# W600X.net
KiCad netlist of a schematic drawn in EAGLE
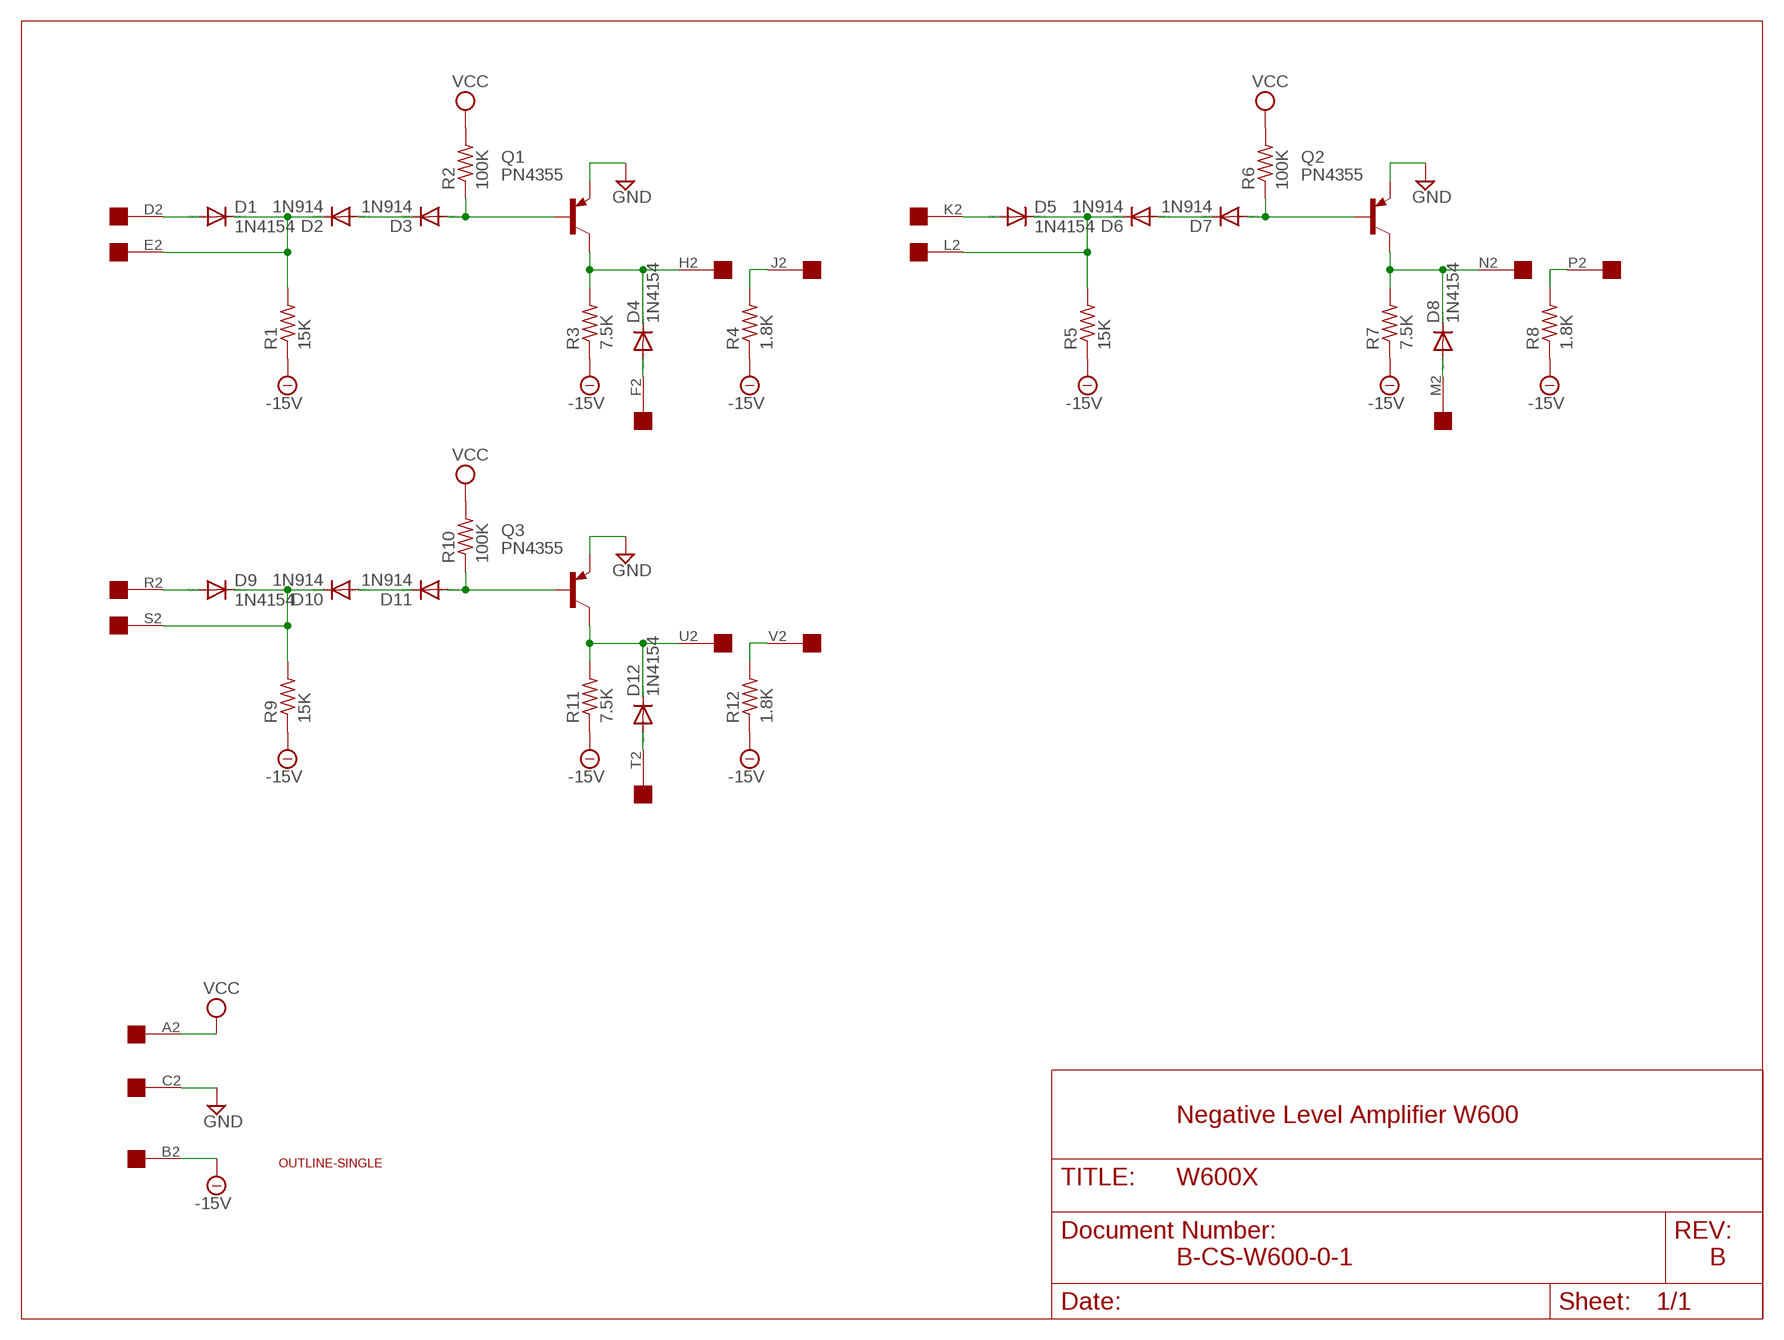
[diagram p0: schematic, sheet 1]

(export (version "E")
  (design (tool "Eeschema 10.0.6"))
  (components
    (comp (ref "D1")
      (value "1N4154")
      (footprint "eagle-import:DO35-10")
      (libsource (lib "eagle-import") (part "DIODE-DO35-10"))
    )
    (comp (ref "D2")
      (value "1N914")
      (footprint "eagle-import:DO35-10")
      (libsource (lib "eagle-import") (part "DIODE-DO35-10"))
    )
    (comp (ref "D3")
      (value "1N914")
      (footprint "eagle-import:DO35-10")
      (libsource (lib "eagle-import") (part "DIODE-DO35-10"))
    )
    (comp (ref "D4")
      (value "1N4154")
      (footprint "eagle-import:DO35-10")
      (libsource (lib "eagle-import") (part "DIODE-DO35-10"))
    )
    (comp (ref "D5")
      (value "1N4154")
      (footprint "eagle-import:DO35-10")
      (libsource (lib "eagle-import") (part "DIODE-DO35-10"))
    )
    (comp (ref "D6")
      (value "1N914")
      (footprint "eagle-import:DO35-10")
      (libsource (lib "eagle-import") (part "DIODE-DO35-10"))
    )
    (comp (ref "D7")
      (value "1N914")
      (footprint "eagle-import:DO35-10")
      (libsource (lib "eagle-import") (part "DIODE-DO35-10"))
    )
    (comp (ref "D8")
      (value "1N4154")
      (footprint "eagle-import:DO35-10")
      (libsource (lib "eagle-import") (part "DIODE-DO35-10"))
    )
    (comp (ref "D9")
      (value "1N4154")
      (footprint "eagle-import:DO35-10")
      (libsource (lib "eagle-import") (part "DIODE-DO35-10"))
    )
    (comp (ref "D10")
      (value "1N914")
      (footprint "eagle-import:DO35-10")
      (libsource (lib "eagle-import") (part "DIODE-DO35-10"))
    )
    (comp (ref "D11")
      (value "1N914")
      (footprint "eagle-import:DO35-10")
      (libsource (lib "eagle-import") (part "DIODE-DO35-10"))
    )
    (comp (ref "D12")
      (value "1N4154")
      (footprint "eagle-import:DO35-10")
      (libsource (lib "eagle-import") (part "DIODE-DO35-10"))
    )
    (comp (ref "Q1")
      (value "PN4355")
      (footprint "eagle-import:TO5")
      (libsource (lib "eagle-import") (part "-PNP-TO5"))
    )
    (comp (ref "Q2")
      (value "PN4355")
      (footprint "eagle-import:TO5")
      (libsource (lib "eagle-import") (part "-PNP-TO5"))
    )
    (comp (ref "Q3")
      (value "PN4355")
      (footprint "eagle-import:TO5")
      (libsource (lib "eagle-import") (part "-PNP-TO5"))
    )
    (comp (ref "R1")
      (value "15K")
      (footprint "eagle-import:0207_10")
      (libsource (lib "eagle-import") (part "R-US_0207/10"))
    )
    (comp (ref "R2")
      (value "100K")
      (footprint "eagle-import:0207_10")
      (libsource (lib "eagle-import") (part "R-US_0207/10"))
    )
    (comp (ref "R3")
      (value "7.5K")
      (footprint "eagle-import:0207_10")
      (libsource (lib "eagle-import") (part "R-US_0207/10"))
    )
    (comp (ref "R4")
      (value "1.8K")
      (footprint "eagle-import:0207_10")
      (libsource (lib "eagle-import") (part "R-US_0207/10"))
    )
    (comp (ref "R5")
      (value "15K")
      (footprint "eagle-import:0207_10")
      (libsource (lib "eagle-import") (part "R-US_0207/10"))
    )
    (comp (ref "R6")
      (value "100K")
      (footprint "eagle-import:0207_10")
      (libsource (lib "eagle-import") (part "R-US_0207/10"))
    )
    (comp (ref "R7")
      (value "7.5K")
      (footprint "eagle-import:0207_10")
      (libsource (lib "eagle-import") (part "R-US_0207/10"))
    )
    (comp (ref "R8")
      (value "1.8K")
      (footprint "eagle-import:0207_10")
      (libsource (lib "eagle-import") (part "R-US_0207/10"))
    )
    (comp (ref "R9")
      (value "15K")
      (footprint "eagle-import:0207_10")
      (libsource (lib "eagle-import") (part "R-US_0207/10"))
    )
    (comp (ref "R10")
      (value "100K")
      (footprint "eagle-import:0207_10")
      (libsource (lib "eagle-import") (part "R-US_0207/10"))
    )
    (comp (ref "R11")
      (value "7.5K")
      (footprint "eagle-import:0207_10")
      (libsource (lib "eagle-import") (part "R-US_0207/10"))
    )
    (comp (ref "R12")
      (value "1.8K")
      (footprint "eagle-import:0207_10")
      (libsource (lib "eagle-import") (part "R-US_0207/10"))
    )
    (comp (ref "U$1")
      (value "OUTLINE-SINGLE")
      (footprint "eagle-import:SINGLE")
      (libsource (lib "eagle-import") (part "OUTLINE-SINGLE"))
    )
    (comp (ref "U$2")
      (value "EDGE-1")
      (footprint "eagle-import:EDGE-CON1")
      (libsource (lib "eagle-import") (part "EDGE-1"))
    )
  )
  (nets
    (net (code "1") (name "-15V") (class "Default")
      (node (ref "R1") (pin "1") (pinfunction "1_1") (pintype "passive"))
      (node (ref "R11") (pin "1") (pinfunction "1_1") (pintype "passive"))
      (node (ref "R12") (pin "1") (pinfunction "1_1") (pintype "passive"))
      (node (ref "R3") (pin "1") (pinfunction "1_1") (pintype "passive"))
      (node (ref "R4") (pin "1") (pinfunction "1_1") (pintype "passive"))
      (node (ref "R5") (pin "1") (pinfunction "1_1") (pintype "passive"))
      (node (ref "R7") (pin "1") (pinfunction "1_1") (pintype "passive"))
      (node (ref "R8") (pin "1") (pinfunction "1_1") (pintype "passive"))
      (node (ref "R9") (pin "1") (pinfunction "1_1") (pintype "passive"))
      (node (ref "U$2") (pin "B2") (pinfunction "1_B2") (pintype "bidirectional"))
    )
    (net (code "2") (name "GND") (class "Default")
      (node (ref "Q1") (pin "1") (pinfunction "E_1") (pintype "passive"))
      (node (ref "Q2") (pin "1") (pinfunction "E_1") (pintype "passive"))
      (node (ref "Q3") (pin "1") (pinfunction "E_1") (pintype "passive"))
      (node (ref "U$2") (pin "C2") (pinfunction "1_C2") (pintype "bidirectional"))
    )
    (net (code "3") (name "Net-(D2-PadA)") (class "Default")
      (node (ref "D2") (pin "A") (pinfunction "A_A") (pintype "passive"))
      (node (ref "D3") (pin "C") (pinfunction "C_C") (pintype "passive"))
    )
    (net (code "4") (name "Net-(D6-PadA)") (class "Default")
      (node (ref "D6") (pin "A") (pinfunction "A_A") (pintype "passive"))
      (node (ref "D7") (pin "C") (pinfunction "C_C") (pintype "passive"))
    )
    (net (code "5") (name "Net-(D10-PadA)") (class "Default")
      (node (ref "D10") (pin "A") (pinfunction "A_A") (pintype "passive"))
      (node (ref "D11") (pin "C") (pinfunction "C_C") (pintype "passive"))
    )
    (net (code "6") (name "Net-(Q1-B)") (class "Default")
      (node (ref "D3") (pin "A") (pinfunction "A_A") (pintype "passive"))
      (node (ref "Q1") (pin "2") (pinfunction "B_2") (pintype "passive"))
      (node (ref "R2") (pin "1") (pinfunction "1_1") (pintype "passive"))
    )
    (net (code "7") (name "Net-(Q1-C)") (class "Default")
      (node (ref "D4") (pin "C") (pinfunction "C_C") (pintype "passive"))
      (node (ref "Q1") (pin "3") (pinfunction "C_3") (pintype "passive"))
      (node (ref "R3") (pin "2") (pinfunction "2_2") (pintype "passive"))
      (node (ref "U$2") (pin "H2") (pinfunction "1_H2") (pintype "bidirectional"))
    )
    (net (code "8") (name "Net-(Q2-B)") (class "Default")
      (node (ref "D7") (pin "A") (pinfunction "A_A") (pintype "passive"))
      (node (ref "Q2") (pin "2") (pinfunction "B_2") (pintype "passive"))
      (node (ref "R6") (pin "1") (pinfunction "1_1") (pintype "passive"))
    )
    (net (code "9") (name "Net-(Q2-C)") (class "Default")
      (node (ref "D8") (pin "C") (pinfunction "C_C") (pintype "passive"))
      (node (ref "Q2") (pin "3") (pinfunction "C_3") (pintype "passive"))
      (node (ref "R7") (pin "2") (pinfunction "2_2") (pintype "passive"))
      (node (ref "U$2") (pin "N2") (pinfunction "1_N2") (pintype "bidirectional"))
    )
    (net (code "10") (name "Net-(Q3-B)") (class "Default")
      (node (ref "D11") (pin "A") (pinfunction "A_A") (pintype "passive"))
      (node (ref "Q3") (pin "2") (pinfunction "B_2") (pintype "passive"))
      (node (ref "R10") (pin "1") (pinfunction "1_1") (pintype "passive"))
    )
    (net (code "11") (name "Net-(Q3-C)") (class "Default")
      (node (ref "D12") (pin "C") (pinfunction "C_C") (pintype "passive"))
      (node (ref "Q3") (pin "3") (pinfunction "C_3") (pintype "passive"))
      (node (ref "R11") (pin "2") (pinfunction "2_2") (pintype "passive"))
      (node (ref "U$2") (pin "U2") (pinfunction "1_U2") (pintype "bidirectional"))
    )
    (net (code "12") (name "Net-(U$2D-1)") (class "Default")
      (node (ref "D1") (pin "A") (pinfunction "A_A") (pintype "passive"))
      (node (ref "U$2") (pin "D2") (pinfunction "1_D2") (pintype "bidirectional"))
    )
    (net (code "13") (name "Net-(U$2E-1)") (class "Default")
      (node (ref "D1") (pin "C") (pinfunction "C_C") (pintype "passive"))
      (node (ref "D2") (pin "C") (pinfunction "C_C") (pintype "passive"))
      (node (ref "R1") (pin "2") (pinfunction "2_2") (pintype "passive"))
      (node (ref "U$2") (pin "E2") (pinfunction "1_E2") (pintype "bidirectional"))
    )
    (net (code "14") (name "Net-(U$2F-1)") (class "Default")
      (node (ref "D4") (pin "A") (pinfunction "A_A") (pintype "passive"))
      (node (ref "U$2") (pin "F2") (pinfunction "1_F2") (pintype "bidirectional"))
    )
    (net (code "15") (name "Net-(U$2H-1)") (class "Default")
      (node (ref "R4") (pin "2") (pinfunction "2_2") (pintype "passive"))
      (node (ref "U$2") (pin "J2") (pinfunction "1_J2") (pintype "bidirectional"))
    )
    (net (code "16") (name "Net-(U$2I-1)") (class "Default")
      (node (ref "D5") (pin "A") (pinfunction "A_A") (pintype "passive"))
      (node (ref "U$2") (pin "K2") (pinfunction "1_K2") (pintype "bidirectional"))
    )
    (net (code "17") (name "Net-(U$2J-1)") (class "Default")
      (node (ref "D5") (pin "C") (pinfunction "C_C") (pintype "passive"))
      (node (ref "D6") (pin "C") (pinfunction "C_C") (pintype "passive"))
      (node (ref "R5") (pin "2") (pinfunction "2_2") (pintype "passive"))
      (node (ref "U$2") (pin "L2") (pinfunction "1_L2") (pintype "bidirectional"))
    )
    (net (code "18") (name "Net-(U$2K-1)") (class "Default")
      (node (ref "D8") (pin "A") (pinfunction "A_A") (pintype "passive"))
      (node (ref "U$2") (pin "M2") (pinfunction "1_M2") (pintype "bidirectional"))
    )
    (net (code "19") (name "Net-(U$2M-1)") (class "Default")
      (node (ref "R8") (pin "2") (pinfunction "2_2") (pintype "passive"))
      (node (ref "U$2") (pin "P2") (pinfunction "1_P2") (pintype "bidirectional"))
    )
    (net (code "20") (name "Net-(U$2N-1)") (class "Default")
      (node (ref "D9") (pin "A") (pinfunction "A_A") (pintype "passive"))
      (node (ref "U$2") (pin "R2") (pinfunction "1_R2") (pintype "bidirectional"))
    )
    (net (code "21") (name "Net-(U$2O-1)") (class "Default")
      (node (ref "D10") (pin "C") (pinfunction "C_C") (pintype "passive"))
      (node (ref "D9") (pin "C") (pinfunction "C_C") (pintype "passive"))
      (node (ref "R9") (pin "2") (pinfunction "2_2") (pintype "passive"))
      (node (ref "U$2") (pin "S2") (pinfunction "1_S2") (pintype "bidirectional"))
    )
    (net (code "22") (name "Net-(U$2P-1)") (class "Default")
      (node (ref "D12") (pin "A") (pinfunction "A_A") (pintype "passive"))
      (node (ref "U$2") (pin "T2") (pinfunction "1_T2") (pintype "bidirectional"))
    )
    (net (code "23") (name "Net-(U$2R-1)") (class "Default")
      (node (ref "R12") (pin "2") (pinfunction "2_2") (pintype "passive"))
      (node (ref "U$2") (pin "V2") (pinfunction "1_V2") (pintype "bidirectional"))
    )
    (net (code "24") (name "VCC") (class "Default")
      (node (ref "R10") (pin "2") (pinfunction "2_2") (pintype "passive"))
      (node (ref "R2") (pin "2") (pinfunction "2_2") (pintype "passive"))
      (node (ref "R6") (pin "2") (pinfunction "2_2") (pintype "passive"))
      (node (ref "U$2") (pin "A2") (pinfunction "1_A2") (pintype "bidirectional"))
    )
  )
)
